# XTXBoard.net
KiCad netlist of a schematic drawn in Altium Designer
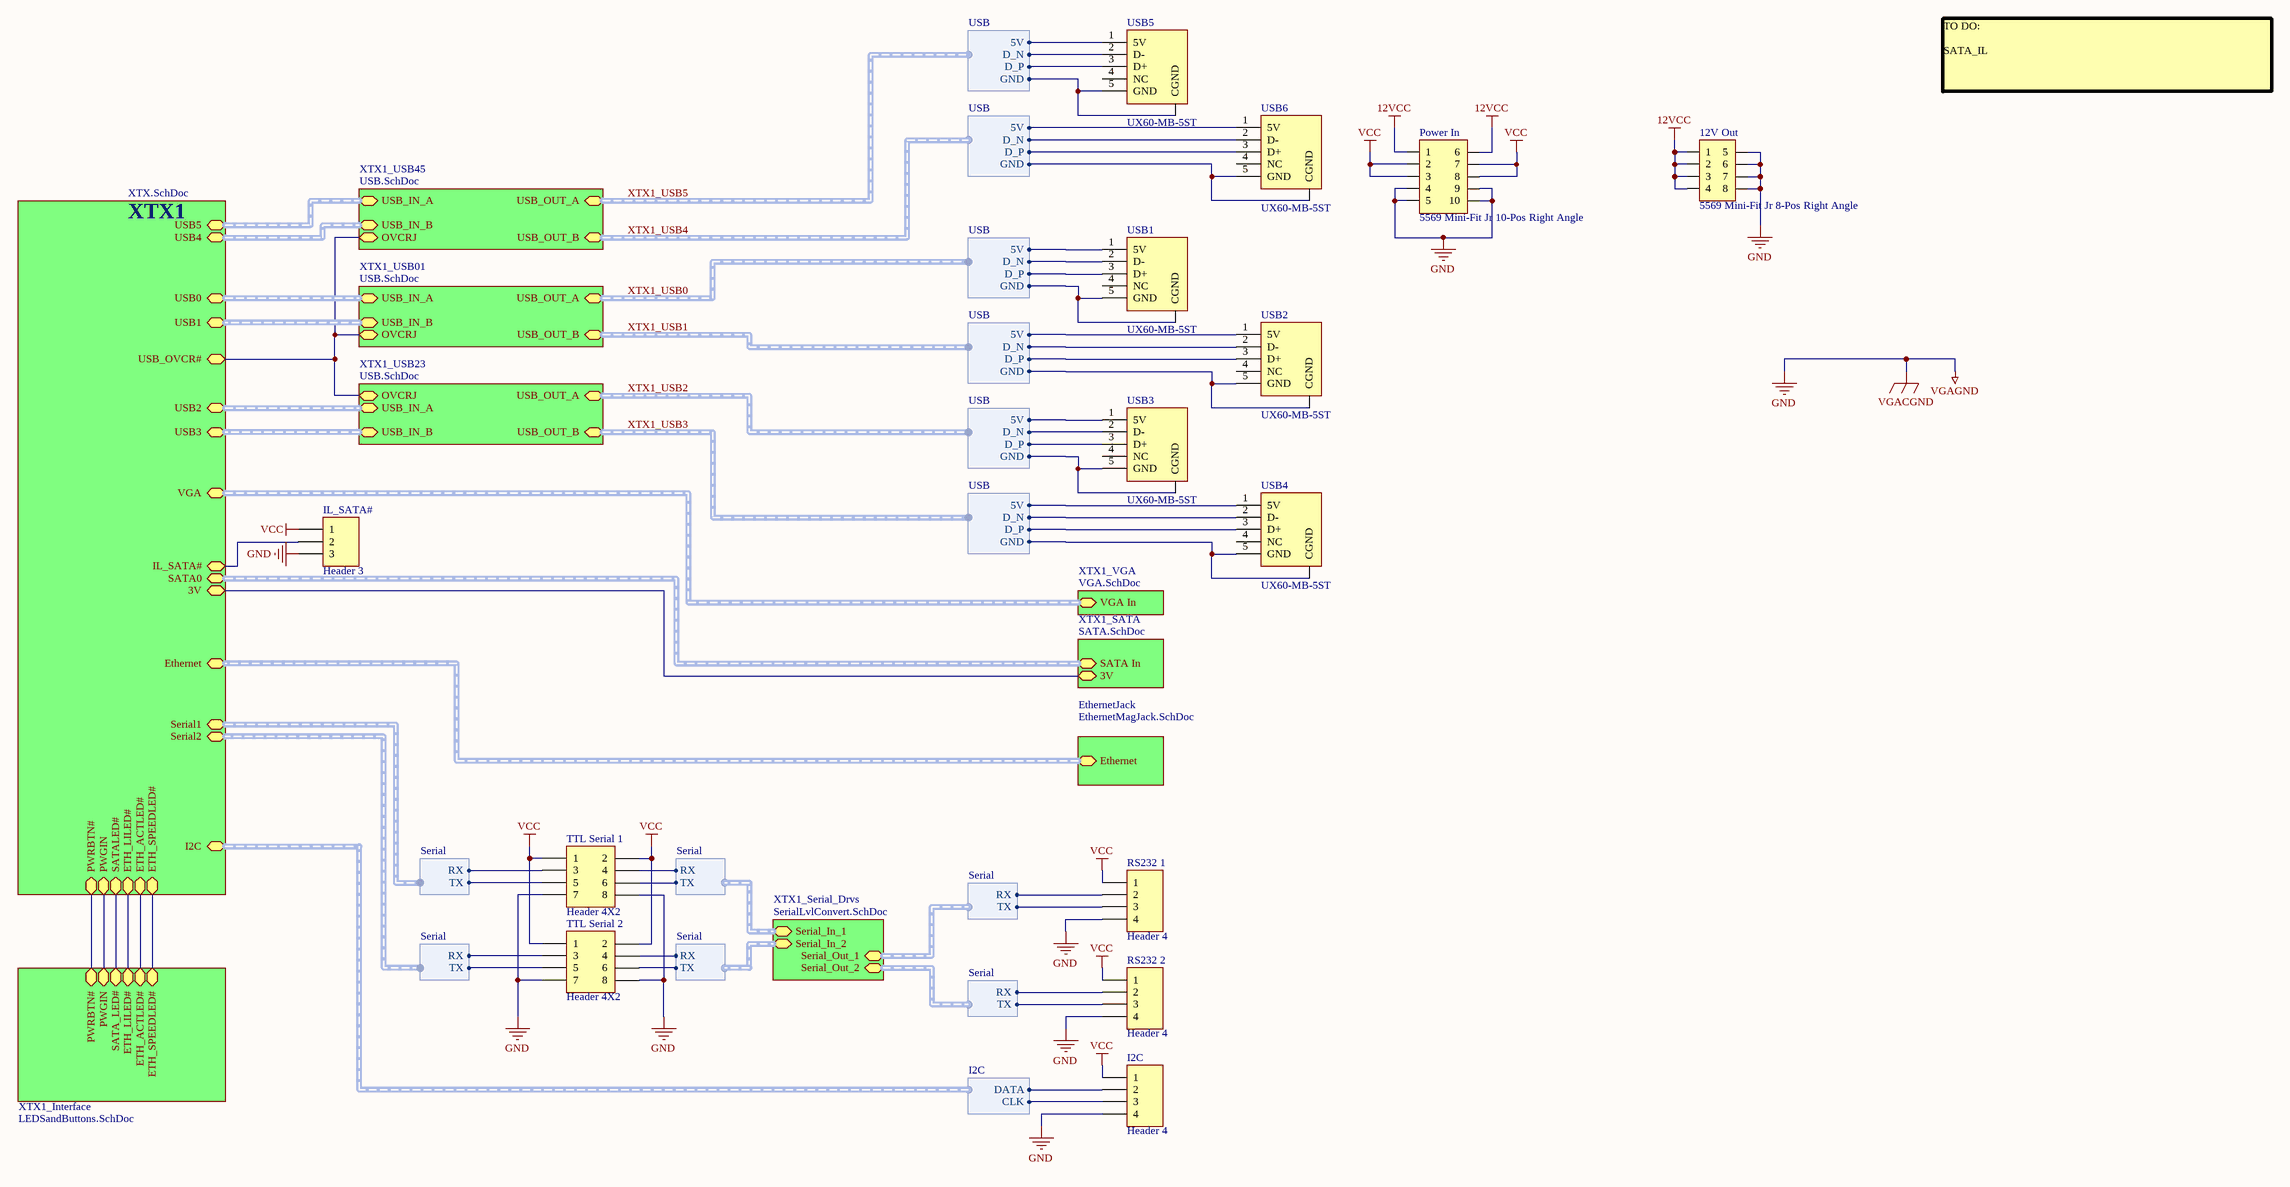
[diagram p0: XTXBoard.SchDoc]

(export (version "E")
  (design (tool "Eeschema 10.0.6"))
  (components
    (comp (ref "12V Out")
      (value "5569 Mini-Fit Jr 8-Pos Right Angle")
      (footprint "MolexConnectors:8-POS 5569 Mini-Fit Jr 2")
      (libsource (lib "Molex") (part "5569 Mini-Fit Jr 8-Pos Right Angle"))
    )
    (comp (ref "I2C")
      (value "Header 4")
      (footprint "HDR1X4")
      (description "Header, 4-Pin")
      (fields (field (name "PUBLISHER") "Altium Limited"))
      (libsource (lib "Miscellaneous Connectors") (part "Header 4"))
    )
    (comp (ref "IL_SATA#")
      (value "Header 3")
      (footprint "HDR1X3")
      (description "Header, 3-Pin")
      (fields (field (name "PUBLISHER") "Altium Limited"))
      (libsource (lib "Miscellaneous Connectors") (part "Header 3"))
    )
    (comp (ref "Power In")
      (value "5569 Mini-Fit Jr 10-Pos Right Angle")
      (footprint "MolexConnectors:10-Pos 5569 Mini-Fit Jr 2")
      (libsource (lib "Molex") (part "5569 Mini-Fit Jr 10-Pos Right Angle"))
    )
    (comp (ref "RS232 1")
      (value "Header 4")
      (footprint "HDR1X4")
      (description "Header, 4-Pin")
      (fields (field (name "PUBLISHER") "Altium Limited"))
      (libsource (lib "Miscellaneous Connectors") (part "Header 4"))
    )
    (comp (ref "RS232 2")
      (value "Header 4")
      (footprint "HDR1X4")
      (description "Header, 4-Pin")
      (fields (field (name "PUBLISHER") "Altium Limited"))
      (libsource (lib "Miscellaneous Connectors") (part "Header 4"))
    )
    (comp (ref "TTL Serial 1")
      (value "Header 4X2")
      (footprint "HDR2X4")
      (description "Header, 4-Pin, Dual row")
      (fields (field (name "PUBLISHER") "Altium Limited"))
      (libsource (lib "Miscellaneous Connectors") (part "Header 4X2"))
    )
    (comp (ref "TTL Serial 2")
      (value "Header 4X2")
      (footprint "HDR2X4")
      (description "Header, 4-Pin, Dual row")
      (fields (field (name "PUBLISHER") "Altium Limited"))
      (libsource (lib "Miscellaneous Connectors") (part "Header 4X2"))
    )
    (comp (ref "USB1")
      (value "UX60-MB-5ST")
      (footprint "Hirose:UX60-MB-5ST")
      (description "miniUSB Type B SMT Connector")
      (libsource (lib "Hirose") (part "UX60-MB-5ST"))
    )
    (comp (ref "USB2")
      (value "UX60-MB-5ST")
      (footprint "Hirose:UX60-MB-5ST")
      (description "miniUSB Type B SMT Connector")
      (libsource (lib "Hirose") (part "UX60-MB-5ST"))
    )
    (comp (ref "USB3")
      (value "UX60-MB-5ST")
      (footprint "Hirose:UX60-MB-5ST")
      (description "miniUSB Type B SMT Connector")
      (libsource (lib "Hirose") (part "UX60-MB-5ST"))
    )
    (comp (ref "USB4")
      (value "UX60-MB-5ST")
      (footprint "Hirose:UX60-MB-5ST")
      (description "miniUSB Type B SMT Connector")
      (libsource (lib "Hirose") (part "UX60-MB-5ST"))
    )
    (comp (ref "USB5")
      (value "UX60-MB-5ST")
      (footprint "Hirose:UX60-MB-5ST")
      (description "miniUSB Type B SMT Connector")
      (libsource (lib "Hirose") (part "UX60-MB-5ST"))
    )
    (comp (ref "USB6")
      (value "UX60-MB-5ST")
      (footprint "Hirose:UX60-MB-5ST")
      (description "miniUSB Type B SMT Connector")
      (libsource (lib "Hirose") (part "UX60-MB-5ST"))
    )
  )
  (nets
    (net (code "10") (name "/CLK") (class "Default")
      (node (ref "I2C") (pin "3") (pinfunction "3_3") (pintype "passive"))
    )
    (net (code "11") (name "/DATA") (class "Default")
      (node (ref "I2C") (pin "2") (pinfunction "2_2") (pintype "passive"))
    )
    (net (code "16") (name "/IL_SATA#") (class "Default")
      (node (ref "IL_SATA#") (pin "2") (pinfunction "2_2") (pintype "passive"))
    )
    (net (code "37") (name "12VCC") (class "Default")
      (node (ref "12V Out") (pin "1") (pinfunction "1_1") (pintype "passive"))
      (node (ref "12V Out") (pin "2") (pinfunction "2_2") (pintype "passive"))
      (node (ref "12V Out") (pin "3") (pinfunction "3_3") (pintype "passive"))
      (node (ref "12V Out") (pin "4") (pinfunction "4_4") (pintype "passive"))
      (node (ref "Power In") (pin "1") (pinfunction "1_1") (pintype "passive"))
      (node (ref "Power In") (pin "6") (pinfunction "6_6") (pintype "passive"))
    )
    (net (code "38") (name "GND") (class "Default")
      (node (ref "12V Out") (pin "5") (pinfunction "5_5") (pintype "passive"))
      (node (ref "12V Out") (pin "6") (pinfunction "6_6") (pintype "passive"))
      (node (ref "12V Out") (pin "7") (pinfunction "7_7") (pintype "passive"))
      (node (ref "12V Out") (pin "8") (pinfunction "8_8") (pintype "passive"))
      (node (ref "I2C") (pin "4") (pinfunction "4_4") (pintype "passive"))
      (node (ref "IL_SATA#") (pin "3") (pinfunction "3_3") (pintype "passive"))
      (node (ref "Power In") (pin "10") (pinfunction "10_10") (pintype "passive"))
      (node (ref "Power In") (pin "4") (pinfunction "4_4") (pintype "passive"))
      (node (ref "Power In") (pin "5") (pinfunction "5_5") (pintype "passive"))
      (node (ref "Power In") (pin "9") (pinfunction "9_9") (pintype "passive"))
      (node (ref "RS232 1") (pin "4") (pinfunction "4_4") (pintype "passive"))
      (node (ref "RS232 2") (pin "4") (pinfunction "4_4") (pintype "passive"))
      (node (ref "TTL Serial 1") (pin "7") (pinfunction "7_7") (pintype "passive"))
      (node (ref "TTL Serial 1") (pin "8") (pinfunction "8_8") (pintype "passive"))
      (node (ref "TTL Serial 2") (pin "7") (pinfunction "7_7") (pintype "passive"))
      (node (ref "TTL Serial 2") (pin "8") (pinfunction "8_8") (pintype "passive"))
    )
    (net (code "39") (name "Net-(USB1-GND)") (class "Default")
      (node (ref "USB1") (pin "5") (pinfunction "GND_5") (pintype "passive"))
      (node (ref "USB1") (pin "CGND") (pinfunction "CGND_CGND") (pintype "passive"))
    )
    (net (code "40") (name "Net-(USB2-GND)") (class "Default")
      (node (ref "USB2") (pin "5") (pinfunction "GND_5") (pintype "passive"))
      (node (ref "USB2") (pin "CGND") (pinfunction "CGND_CGND") (pintype "passive"))
    )
    (net (code "41") (name "Net-(USB3-GND)") (class "Default")
      (node (ref "USB3") (pin "5") (pinfunction "GND_5") (pintype "passive"))
      (node (ref "USB3") (pin "CGND") (pinfunction "CGND_CGND") (pintype "passive"))
    )
    (net (code "42") (name "Net-(USB4-GND)") (class "Default")
      (node (ref "USB4") (pin "5") (pinfunction "GND_5") (pintype "passive"))
      (node (ref "USB4") (pin "CGND") (pinfunction "CGND_CGND") (pintype "passive"))
    )
    (net (code "43") (name "Net-(USB5-GND)") (class "Default")
      (node (ref "USB5") (pin "5") (pinfunction "GND_5") (pintype "passive"))
      (node (ref "USB5") (pin "CGND") (pinfunction "CGND_CGND") (pintype "passive"))
    )
    (net (code "44") (name "Net-(USB6-GND)") (class "Default")
      (node (ref "USB6") (pin "5") (pinfunction "GND_5") (pintype "passive"))
      (node (ref "USB6") (pin "CGND") (pinfunction "CGND_CGND") (pintype "passive"))
    )
    (net (code "45") (name "VCC") (class "Default")
      (node (ref "I2C") (pin "1") (pinfunction "1_1") (pintype "passive"))
      (node (ref "IL_SATA#") (pin "1") (pinfunction "1_1") (pintype "passive"))
      (node (ref "Power In") (pin "2") (pinfunction "2_2") (pintype "passive"))
      (node (ref "Power In") (pin "3") (pinfunction "3_3") (pintype "passive"))
      (node (ref "Power In") (pin "7") (pinfunction "7_7") (pintype "passive"))
      (node (ref "Power In") (pin "8") (pinfunction "8_8") (pintype "passive"))
      (node (ref "RS232 1") (pin "1") (pinfunction "1_1") (pintype "passive"))
      (node (ref "RS232 2") (pin "1") (pinfunction "1_1") (pintype "passive"))
      (node (ref "TTL Serial 1") (pin "1") (pinfunction "1_1") (pintype "passive"))
      (node (ref "TTL Serial 1") (pin "2") (pinfunction "2_2") (pintype "passive"))
      (node (ref "TTL Serial 2") (pin "1") (pinfunction "1_1") (pintype "passive"))
      (node (ref "TTL Serial 2") (pin "2") (pinfunction "2_2") (pintype "passive"))
    )
    (net (code "46") (name "unconnected-(RS232 1-Pad2)") (class "Default")
      (node (ref "RS232 1") (pin "2") (pinfunction "2_2") (pintype "passive"))
    )
    (net (code "47") (name "unconnected-(RS232 1-Pad3)") (class "Default")
      (node (ref "RS232 1") (pin "3") (pinfunction "3_3") (pintype "passive"))
    )
    (net (code "48") (name "unconnected-(RS232 2-Pad2)") (class "Default")
      (node (ref "RS232 2") (pin "2") (pinfunction "2_2") (pintype "passive"))
    )
    (net (code "49") (name "unconnected-(RS232 2-Pad3)") (class "Default")
      (node (ref "RS232 2") (pin "3") (pinfunction "3_3") (pintype "passive"))
    )
    (net (code "50") (name "unconnected-(TTL Serial 1-Pad3)") (class "Default")
      (node (ref "TTL Serial 1") (pin "3") (pinfunction "3_3") (pintype "passive"))
    )
    (net (code "51") (name "unconnected-(TTL Serial 1-Pad4)") (class "Default")
      (node (ref "TTL Serial 1") (pin "4") (pinfunction "4_4") (pintype "passive"))
    )
    (net (code "52") (name "unconnected-(TTL Serial 1-Pad5)") (class "Default")
      (node (ref "TTL Serial 1") (pin "5") (pinfunction "5_5") (pintype "passive"))
    )
    (net (code "53") (name "unconnected-(TTL Serial 1-Pad6)") (class "Default")
      (node (ref "TTL Serial 1") (pin "6") (pinfunction "6_6") (pintype "passive"))
    )
    (net (code "54") (name "unconnected-(TTL Serial 2-Pad3)") (class "Default")
      (node (ref "TTL Serial 2") (pin "3") (pinfunction "3_3") (pintype "passive"))
    )
    (net (code "55") (name "unconnected-(TTL Serial 2-Pad4)") (class "Default")
      (node (ref "TTL Serial 2") (pin "4") (pinfunction "4_4") (pintype "passive"))
    )
    (net (code "56") (name "unconnected-(TTL Serial 2-Pad5)") (class "Default")
      (node (ref "TTL Serial 2") (pin "5") (pinfunction "5_5") (pintype "passive"))
    )
    (net (code "57") (name "unconnected-(TTL Serial 2-Pad6)") (class "Default")
      (node (ref "TTL Serial 2") (pin "6") (pinfunction "6_6") (pintype "passive"))
    )
    (net (code "58") (name "unconnected-(USB1-5V-Pad1)") (class "Default")
      (node (ref "USB1") (pin "1") (pinfunction "5V_1") (pintype "passive"))
    )
    (net (code "59") (name "unconnected-(USB1-D+-Pad3)") (class "Default")
      (node (ref "USB1") (pin "3") (pinfunction "D+_3") (pintype "passive"))
    )
    (net (code "60") (name "unconnected-(USB1-D--Pad2)") (class "Default")
      (node (ref "USB1") (pin "2") (pinfunction "D-_2") (pintype "passive"))
    )
    (net (code "61") (name "unconnected-(USB1-NC-Pad4)") (class "Default")
      (node (ref "USB1") (pin "4") (pinfunction "NC_4") (pintype "passive"))
    )
    (net (code "62") (name "unconnected-(USB2-5V-Pad1)") (class "Default")
      (node (ref "USB2") (pin "1") (pinfunction "5V_1") (pintype "passive"))
    )
    (net (code "63") (name "unconnected-(USB2-D+-Pad3)") (class "Default")
      (node (ref "USB2") (pin "3") (pinfunction "D+_3") (pintype "passive"))
    )
    (net (code "64") (name "unconnected-(USB2-D--Pad2)") (class "Default")
      (node (ref "USB2") (pin "2") (pinfunction "D-_2") (pintype "passive"))
    )
    (net (code "65") (name "unconnected-(USB2-NC-Pad4)") (class "Default")
      (node (ref "USB2") (pin "4") (pinfunction "NC_4") (pintype "passive"))
    )
    (net (code "66") (name "unconnected-(USB3-5V-Pad1)") (class "Default")
      (node (ref "USB3") (pin "1") (pinfunction "5V_1") (pintype "passive"))
    )
    (net (code "67") (name "unconnected-(USB3-D+-Pad3)") (class "Default")
      (node (ref "USB3") (pin "3") (pinfunction "D+_3") (pintype "passive"))
    )
    (net (code "68") (name "unconnected-(USB3-D--Pad2)") (class "Default")
      (node (ref "USB3") (pin "2") (pinfunction "D-_2") (pintype "passive"))
    )
    (net (code "69") (name "unconnected-(USB3-NC-Pad4)") (class "Default")
      (node (ref "USB3") (pin "4") (pinfunction "NC_4") (pintype "passive"))
    )
    (net (code "70") (name "unconnected-(USB4-5V-Pad1)") (class "Default")
      (node (ref "USB4") (pin "1") (pinfunction "5V_1") (pintype "passive"))
    )
    (net (code "71") (name "unconnected-(USB4-D+-Pad3)") (class "Default")
      (node (ref "USB4") (pin "3") (pinfunction "D+_3") (pintype "passive"))
    )
    (net (code "72") (name "unconnected-(USB4-D--Pad2)") (class "Default")
      (node (ref "USB4") (pin "2") (pinfunction "D-_2") (pintype "passive"))
    )
    (net (code "73") (name "unconnected-(USB4-NC-Pad4)") (class "Default")
      (node (ref "USB4") (pin "4") (pinfunction "NC_4") (pintype "passive"))
    )
    (net (code "74") (name "unconnected-(USB5-5V-Pad1)") (class "Default")
      (node (ref "USB5") (pin "1") (pinfunction "5V_1") (pintype "passive"))
    )
    (net (code "75") (name "unconnected-(USB5-D+-Pad3)") (class "Default")
      (node (ref "USB5") (pin "3") (pinfunction "D+_3") (pintype "passive"))
    )
    (net (code "76") (name "unconnected-(USB5-D--Pad2)") (class "Default")
      (node (ref "USB5") (pin "2") (pinfunction "D-_2") (pintype "passive"))
    )
    (net (code "77") (name "unconnected-(USB5-NC-Pad4)") (class "Default")
      (node (ref "USB5") (pin "4") (pinfunction "NC_4") (pintype "passive"))
    )
    (net (code "78") (name "unconnected-(USB6-5V-Pad1)") (class "Default")
      (node (ref "USB6") (pin "1") (pinfunction "5V_1") (pintype "passive"))
    )
    (net (code "79") (name "unconnected-(USB6-D+-Pad3)") (class "Default")
      (node (ref "USB6") (pin "3") (pinfunction "D+_3") (pintype "passive"))
    )
    (net (code "80") (name "unconnected-(USB6-D--Pad2)") (class "Default")
      (node (ref "USB6") (pin "2") (pinfunction "D-_2") (pintype "passive"))
    )
    (net (code "81") (name "unconnected-(USB6-NC-Pad4)") (class "Default")
      (node (ref "USB6") (pin "4") (pinfunction "NC_4") (pintype "passive"))
    )
  )
)
